# Frequency_synthesizer_v2_0.net
KiCad netlist of a schematic drawn in EAGLE
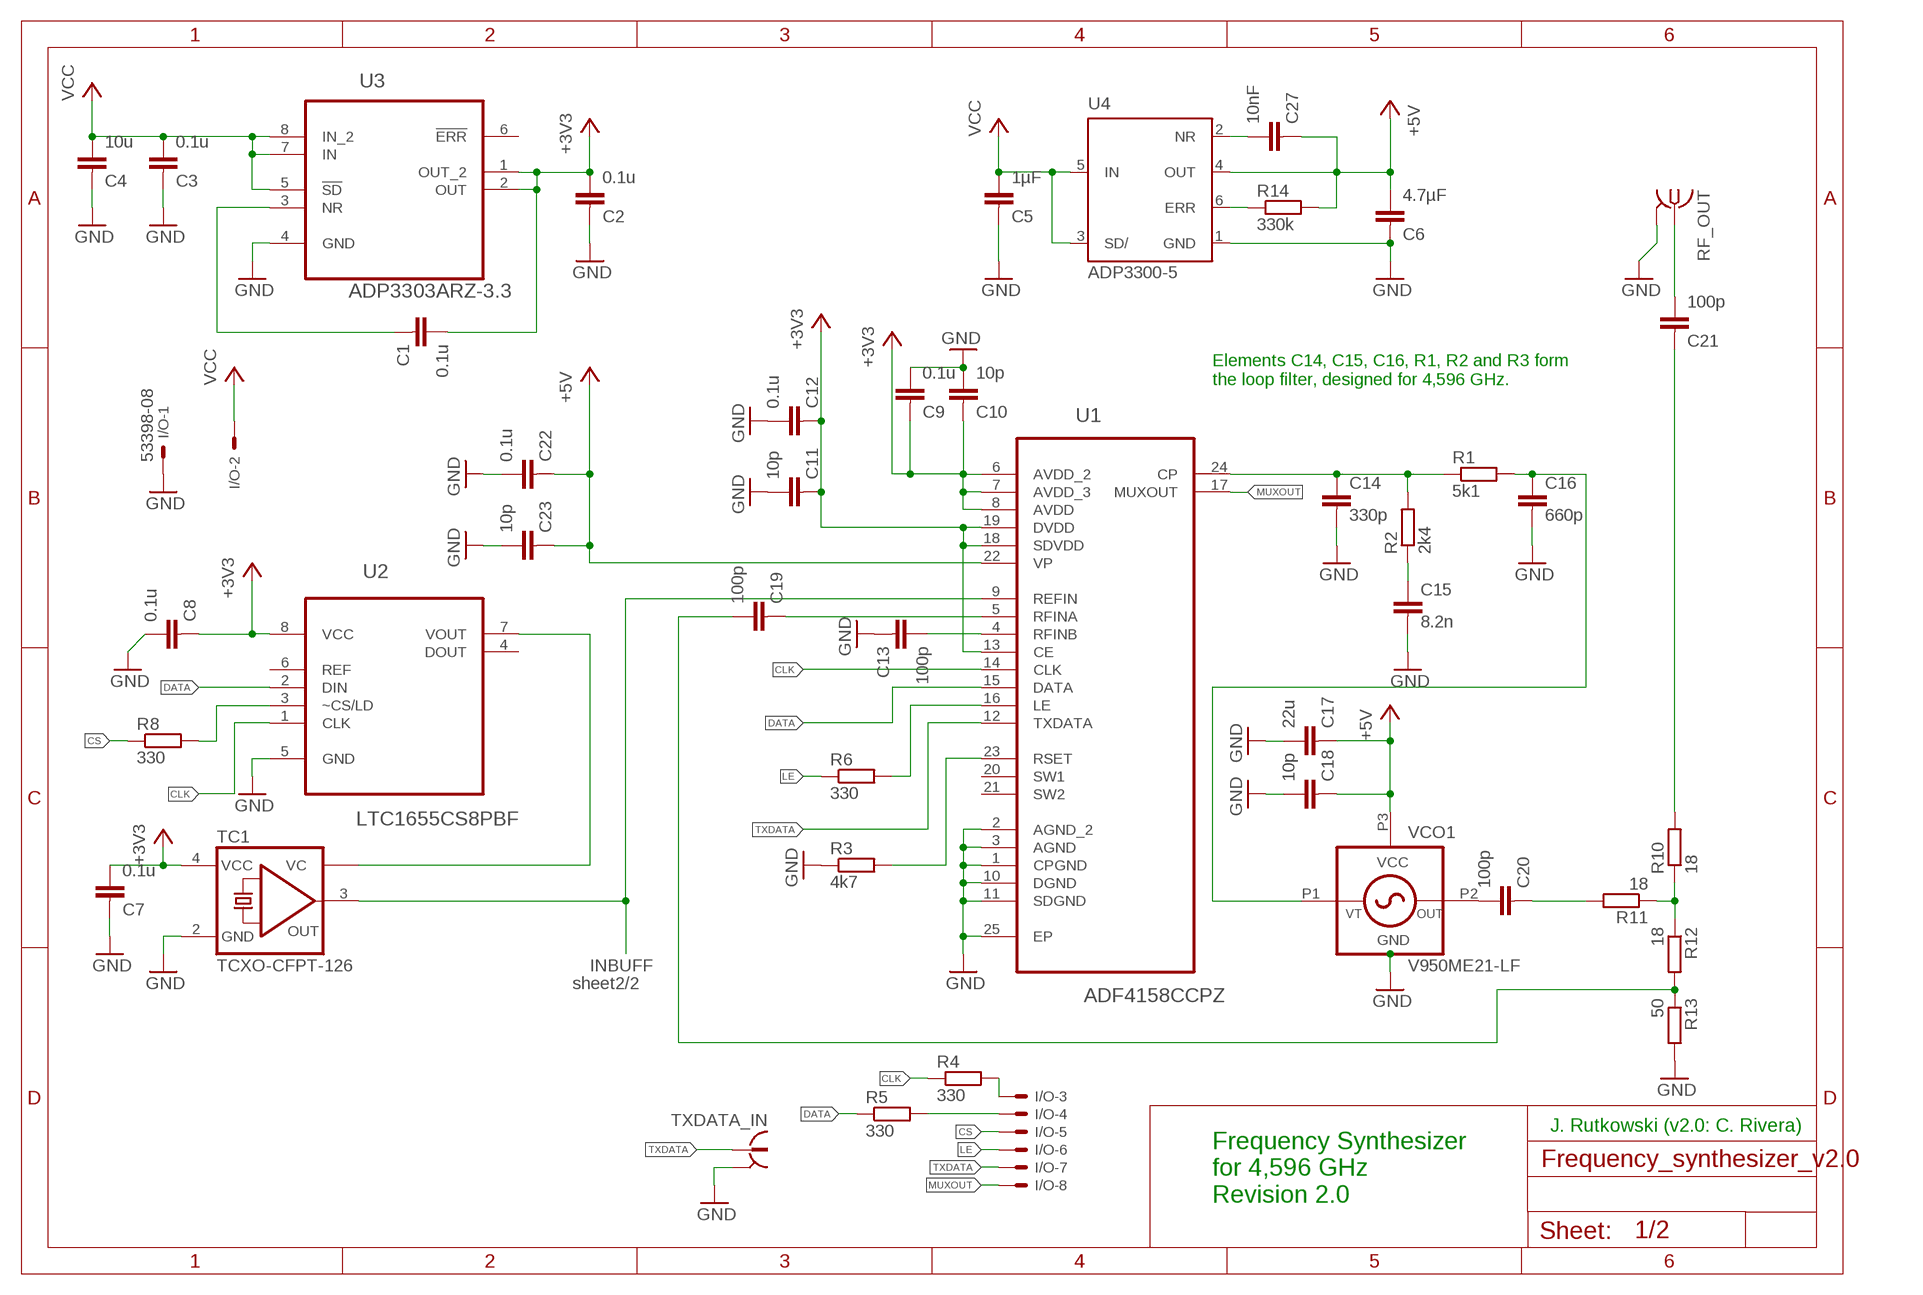
[diagram p0: schematic, sheet 1]
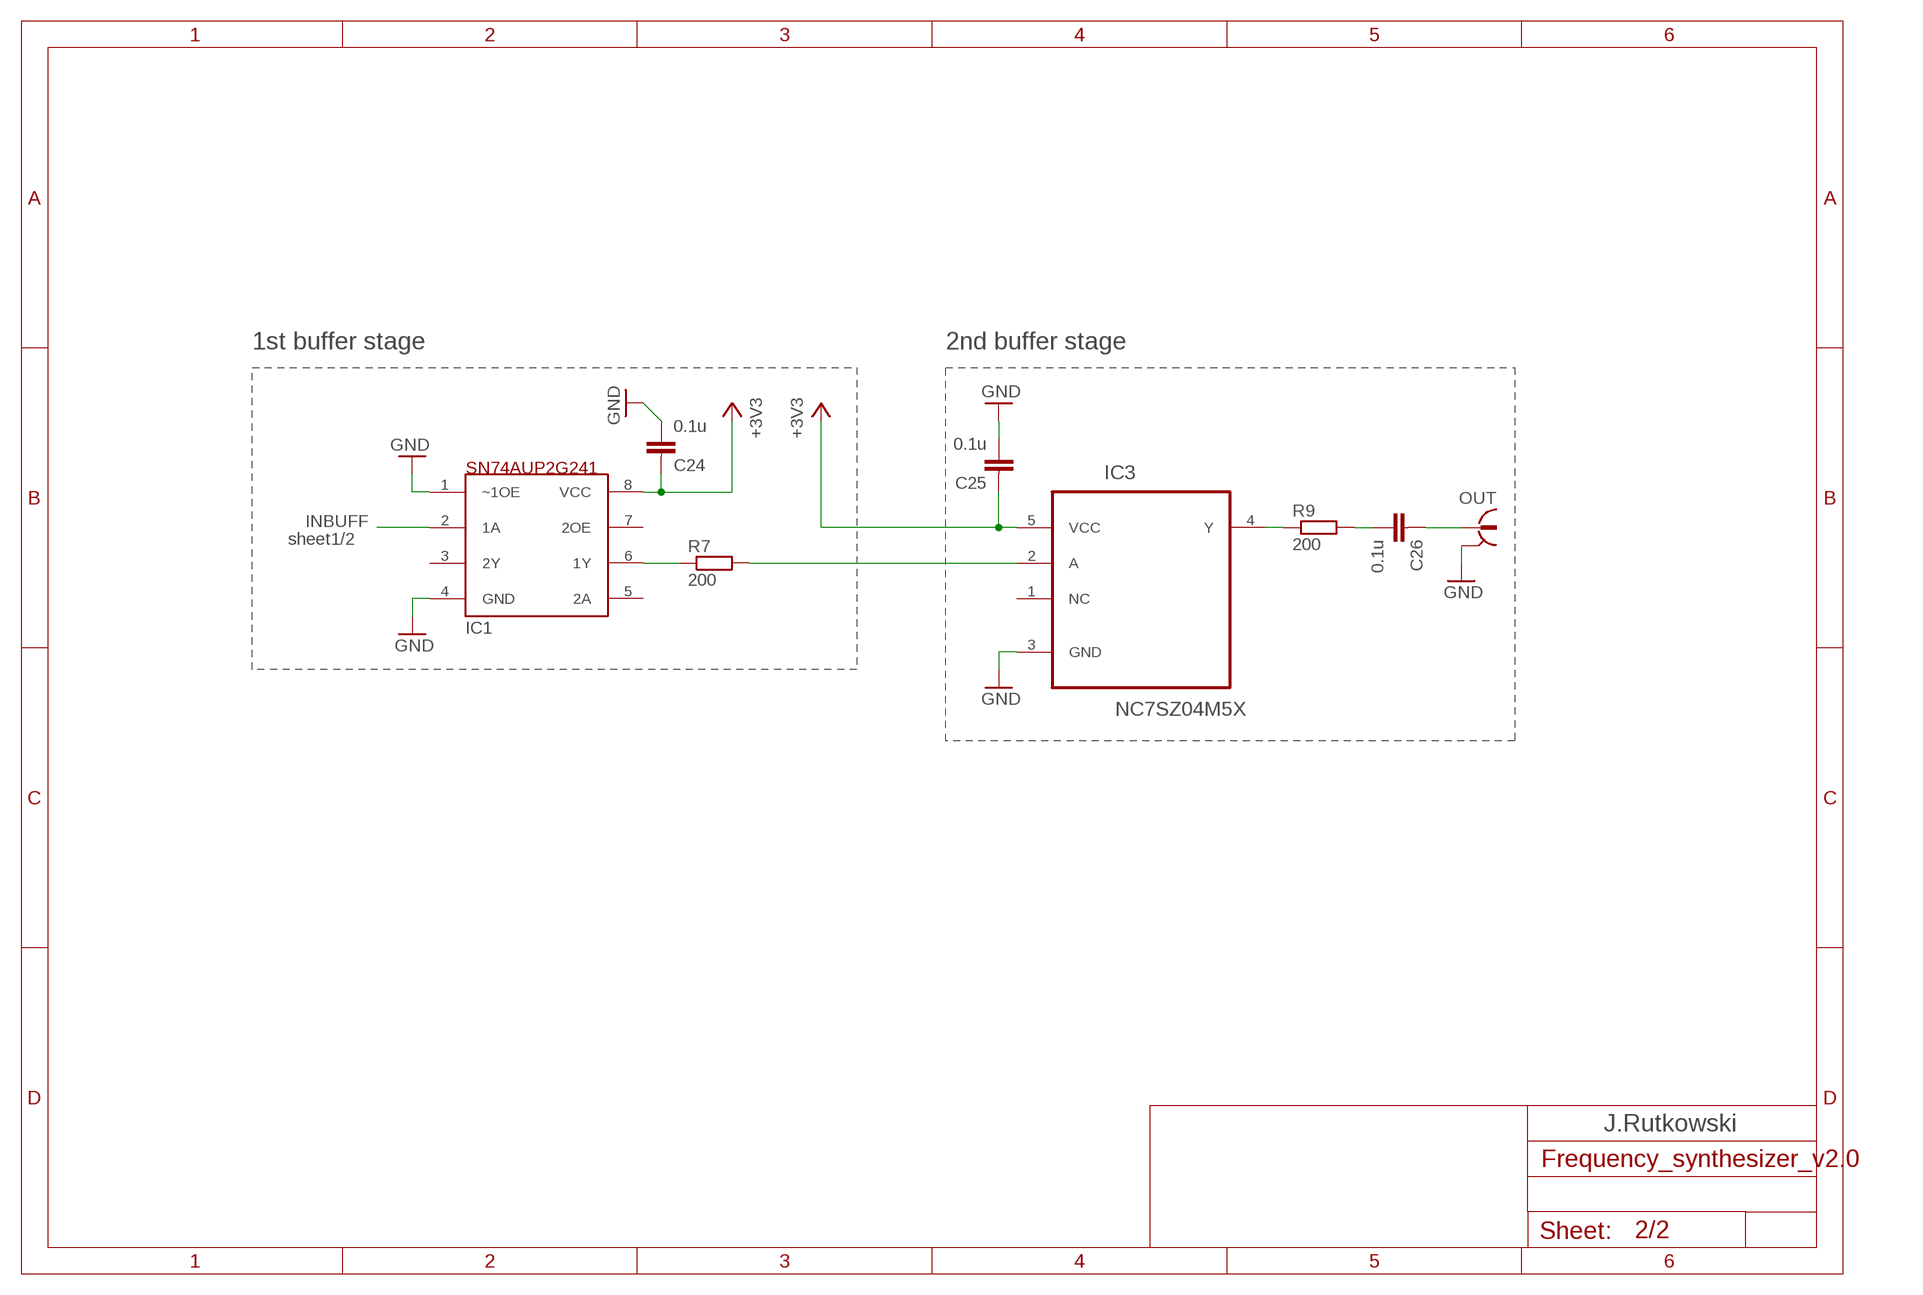
[diagram p1: schematic, sheet 2]

(export (version "E")
  (design (tool "Eeschema 10.0.6"))
  (components
    (comp (ref "C1")
      (value "0.1u")
      (footprint "eagle-import:C0603K")
      (libsource (lib "eagle-import") (part "C-EUC0603K"))
    )
    (comp (ref "C2")
      (value "0.1u")
      (footprint "eagle-import:C0603K")
      (libsource (lib "eagle-import") (part "C-EUC0603K"))
    )
    (comp (ref "C3")
      (value "0.1u")
      (footprint "eagle-import:C0603K")
      (libsource (lib "eagle-import") (part "C-EUC0603K"))
    )
    (comp (ref "C4")
      (value "10u")
      (footprint "eagle-import:C0805K")
      (libsource (lib "eagle-import") (part "C-EUC0805K"))
    )
    (comp (ref "C5")
      (value "1µF")
      (footprint "eagle-import:C0603K")
      (libsource (lib "eagle-import") (part "C-EUC0603K"))
    )
    (comp (ref "C6")
      (value "4.7µF")
      (footprint "eagle-import:C0603K")
      (libsource (lib "eagle-import") (part "C-EUC0603K"))
    )
    (comp (ref "C7")
      (value "0.1u")
      (footprint "eagle-import:C0603K")
      (libsource (lib "eagle-import") (part "C-EUC0603K"))
    )
    (comp (ref "C8")
      (value "0.1u")
      (footprint "eagle-import:C0603K")
      (libsource (lib "eagle-import") (part "C-EUC0603K"))
    )
    (comp (ref "C9")
      (value "0.1u")
      (footprint "eagle-import:C0603K")
      (libsource (lib "eagle-import") (part "C-EUC0603K"))
    )
    (comp (ref "C10")
      (value "10p")
      (footprint "eagle-import:C0603K")
      (libsource (lib "eagle-import") (part "C-EUC0603K"))
    )
    (comp (ref "C11")
      (value "10p")
      (footprint "eagle-import:C0603K")
      (libsource (lib "eagle-import") (part "C-EUC0603K"))
    )
    (comp (ref "C12")
      (value "0.1u")
      (footprint "eagle-import:C0603K")
      (libsource (lib "eagle-import") (part "C-EUC0603K"))
    )
    (comp (ref "C13")
      (value "100p")
      (footprint "eagle-import:C0402")
      (libsource (lib "eagle-import") (part "C-EUC0402"))
    )
    (comp (ref "C14")
      (value "330p")
      (footprint "eagle-import:C0603K")
      (libsource (lib "eagle-import") (part "C-EUC0603K"))
    )
    (comp (ref "C15")
      (value "8.2n")
      (footprint "eagle-import:C0603K")
      (libsource (lib "eagle-import") (part "C-EUC0603K"))
    )
    (comp (ref "C16")
      (value "660p")
      (footprint "eagle-import:C0603K")
      (libsource (lib "eagle-import") (part "C-EUC0603K"))
    )
    (comp (ref "C17")
      (value "22u")
      (footprint "eagle-import:C0805")
      (libsource (lib "eagle-import") (part "C-EUC0805"))
    )
    (comp (ref "C18")
      (value "10p")
      (footprint "eagle-import:C0603K")
      (libsource (lib "eagle-import") (part "C-EUC0603K"))
    )
    (comp (ref "C19")
      (value "100p")
      (footprint "eagle-import:C0402")
      (libsource (lib "eagle-import") (part "C-EUC0402"))
    )
    (comp (ref "C20")
      (value "100p")
      (footprint "eagle-import:C0402")
      (libsource (lib "eagle-import") (part "C-EUC0402"))
    )
    (comp (ref "C21")
      (value "100p")
      (footprint "eagle-import:C0402")
      (libsource (lib "eagle-import") (part "C-EUC0402"))
    )
    (comp (ref "C22")
      (value "0.1u")
      (footprint "eagle-import:C0603K")
      (libsource (lib "eagle-import") (part "C-EUC0603K"))
    )
    (comp (ref "C23")
      (value "10p")
      (footprint "eagle-import:C0603K")
      (libsource (lib "eagle-import") (part "C-EUC0603K"))
    )
    (comp (ref "C27")
      (value "10nF")
      (footprint "eagle-import:C0603K")
      (libsource (lib "eagle-import") (part "C-EUC0603K"))
    )
    (comp (ref "I/O")
      (value "53398-08")
      (footprint "eagle-import:53398-08")
      (libsource (lib "eagle-import") (part "53?-08398"))
    )
    (comp (ref "R1")
      (value "5k1")
      (footprint "eagle-import:R0603")
      (libsource (lib "eagle-import") (part "R-EU_R0603"))
    )
    (comp (ref "R2")
      (value "2k4")
      (footprint "eagle-import:R0603")
      (libsource (lib "eagle-import") (part "R-EU_R0603"))
    )
    (comp (ref "R3")
      (value "4k7")
      (footprint "eagle-import:R0603")
      (libsource (lib "eagle-import") (part "R-EU_R0603"))
    )
    (comp (ref "R4")
      (value "330")
      (footprint "eagle-import:R0603")
      (libsource (lib "eagle-import") (part "R-EU_R0603"))
    )
    (comp (ref "R5")
      (value "330")
      (footprint "eagle-import:R0603")
      (libsource (lib "eagle-import") (part "R-EU_R0603"))
    )
    (comp (ref "R6")
      (value "330")
      (footprint "eagle-import:R0603")
      (libsource (lib "eagle-import") (part "R-EU_R0603"))
    )
    (comp (ref "R8")
      (value "330")
      (footprint "eagle-import:R0603")
      (libsource (lib "eagle-import") (part "R-EU_R0603"))
    )
    (comp (ref "R10")
      (value "18")
      (footprint "eagle-import:R0402")
      (libsource (lib "eagle-import") (part "R-EU_R0402"))
    )
    (comp (ref "R11")
      (value "18")
      (footprint "eagle-import:R0402")
      (libsource (lib "eagle-import") (part "R-EU_R0402"))
    )
    (comp (ref "R12")
      (value "18")
      (footprint "eagle-import:R0402")
      (libsource (lib "eagle-import") (part "R-EU_R0402"))
    )
    (comp (ref "R13")
      (value "50")
      (footprint "eagle-import:R0402")
      (libsource (lib "eagle-import") (part "R-EU_R0402"))
    )
    (comp (ref "R14")
      (value "330k")
      (footprint "eagle-import:R0603")
      (libsource (lib "eagle-import") (part "R-EU_R0603"))
    )
    (comp (ref "RF_OUT")
      (value "SMA-142-0711-871/876")
      (footprint "eagle-import:J502-ND-142-0711-871_876")
      (fields (field (name "MF") "JOHNSON COMPONENTS") (field (name "MPN") "142-0711-871"))
      (libsource (lib "eagle-import") (part "SMA-142-0711-871/876"))
    )
    (comp (ref "TC1")
      (value "TCXO-CFPT-126")
      (footprint "eagle-import:7.0X5.0-4-PAD")
      (libsource (lib "eagle-import") (part "TCXO-CFPT-126"))
    )
    (comp (ref "TXDATA_IN")
      (value "734120110")
      (footprint "eagle-import:734120110")
      (libsource (lib "eagle-import") (part "734120110"))
    )
    (comp (ref "U1")
      (value "ADF4158CCPZ")
      (footprint "eagle-import:QFN50P400X400X80-25N")
      (libsource (lib "eagle-import") (part "ADF4158CCPZ"))
    )
    (comp (ref "U2")
      (value "LTC1655CS8PBF")
      (footprint "eagle-import:SOIC127P600X175-8N")
      (fields (field (name "MPN") "LTC1655CS8#PBF"))
      (libsource (lib "eagle-import") (part "LTC1655CS8PBF"))
    )
    (comp (ref "U3")
      (value "ADP3303ARZ-3.3")
      (footprint "eagle-import:SOIC127P600X175-8N")
      (libsource (lib "eagle-import") (part "ADP3303ARZ-3.3"))
    )
    (comp (ref "U4")
      (value "ADP3300-5")
      (footprint "eagle-import:SOT23-6")
      (libsource (lib "eagle-import") (part "ADP3300-5"))
    )
    (comp (ref "VCO1")
      (value "V950ME21-LF")
      (footprint "eagle-import:MINI-14S")
      (libsource (lib "eagle-import") (part "MINI-14S"))
    )
    (comp (ref "C24")
      (value "0.1u")
      (footprint "eagle-import:C0603K")
      (libsource (lib "eagle-import") (part "C-EUC0603K"))
    )
    (comp (ref "C25")
      (value "0.1u")
      (footprint "eagle-import:C0603K")
      (libsource (lib "eagle-import") (part "C-EUC0603K"))
    )
    (comp (ref "C26")
      (value "0.1u")
      (footprint "eagle-import:C0603K")
      (libsource (lib "eagle-import") (part "C-EUC0603K"))
    )
    (comp (ref "IC1")
      (value "SN74AUP2G241")
      (footprint "eagle-import:DCU_(R-PDSO-G8)")
      (libsource (lib "eagle-import") (part "SN74AUP2G241"))
    )
    (comp (ref "IC3")
      (value "NC7SZ04M5X")
      (footprint "eagle-import:SOT95P280X145-5N")
      (libsource (lib "eagle-import") (part "NC7SZ04M5X"))
    )
    (comp (ref "OUT")
      (value "734120110")
      (footprint "eagle-import:734120110")
      (libsource (lib "eagle-import") (part "734120110"))
    )
    (comp (ref "R7")
      (value "200")
      (footprint "eagle-import:R0603")
      (libsource (lib "eagle-import") (part "R-EU_R0603"))
    )
    (comp (ref "R9")
      (value "200")
      (footprint "eagle-import:R0603")
      (libsource (lib "eagle-import") (part "R-EU_R0603"))
    )
  )
  (nets
    (net (code "1") (name "+3V3") (class "Default")
      (node (ref "C1") (pin "1") (pinfunction "1_1") (pintype "passive"))
      (node (ref "C10") (pin "2") (pinfunction "2_2") (pintype "passive"))
      (node (ref "C11") (pin "2") (pinfunction "2_2") (pintype "passive"))
      (node (ref "C12") (pin "2") (pinfunction "2_2") (pintype "passive"))
      (node (ref "C2") (pin "1") (pinfunction "1_1") (pintype "passive"))
      (node (ref "C24") (pin "2") (pinfunction "2_2") (pintype "passive"))
      (node (ref "C25") (pin "2") (pinfunction "2_2") (pintype "passive"))
      (node (ref "C7") (pin "1") (pinfunction "1_1") (pintype "passive"))
      (node (ref "C8") (pin "2") (pinfunction "2_2") (pintype "passive"))
      (node (ref "C9") (pin "2") (pinfunction "2_2") (pintype "passive"))
      (node (ref "IC1") (pin "8") (pinfunction "VCC_8") (pintype "bidirectional"))
      (node (ref "IC3") (pin "5") (pinfunction "VCC_5") (pintype "power_in"))
      (node (ref "TC1") (pin "4") (pinfunction "VCC_4") (pintype "power_in"))
      (node (ref "U1") (pin "13") (pinfunction "CE_13") (pintype "input"))
      (node (ref "U1") (pin "18") (pinfunction "SDVDD_18") (pintype "power_in"))
      (node (ref "U1") (pin "19") (pinfunction "DVDD_19") (pintype "power_in"))
      (node (ref "U1") (pin "6") (pinfunction "AVDD_2_6") (pintype "power_in"))
      (node (ref "U1") (pin "7") (pinfunction "AVDD_3_7") (pintype "power_in"))
      (node (ref "U1") (pin "8") (pinfunction "AVDD_8") (pintype "power_in"))
      (node (ref "U2") (pin "8") (pinfunction "VCC_8") (pintype "power_in"))
      (node (ref "U3") (pin "1") (pinfunction "OUT_2_1") (pintype "output"))
      (node (ref "U3") (pin "2") (pinfunction "OUT_2") (pintype "output"))
    )
    (net (code "2") (name "+5V") (class "Default")
      (node (ref "C17") (pin "2") (pinfunction "2_2") (pintype "passive"))
      (node (ref "C18") (pin "2") (pinfunction "2_2") (pintype "passive"))
      (node (ref "C22") (pin "2") (pinfunction "2_2") (pintype "passive"))
      (node (ref "C23") (pin "2") (pinfunction "2_2") (pintype "passive"))
      (node (ref "C27") (pin "2") (pinfunction "2_2") (pintype "passive"))
      (node (ref "C6") (pin "1") (pinfunction "1_1") (pintype "passive"))
      (node (ref "R14") (pin "2") (pinfunction "2_2") (pintype "passive"))
      (node (ref "U1") (pin "22") (pinfunction "VP_22") (pintype "power_in"))
      (node (ref "U4") (pin "4") (pinfunction "OUT_4") (pintype "output"))
      (node (ref "VCO1") (pin "P3") (pinfunction "VCC_P3") (pintype "power_in"))
    )
    (net (code "3") (name "CLK") (class "Default")
      (node (ref "R4") (pin "1") (pinfunction "1_1") (pintype "passive"))
      (node (ref "U1") (pin "14") (pinfunction "CLK_14") (pintype "input"))
      (node (ref "U2") (pin "1") (pinfunction "CLK_1") (pintype "input"))
    )
    (net (code "4") (name "CS") (class "Default")
      (node (ref "I/O") (pin "5") (pinfunction "S_5") (pintype "passive"))
      (node (ref "R8") (pin "1") (pinfunction "1_1") (pintype "passive"))
    )
    (net (code "5") (name "DATA") (class "Default")
      (node (ref "R5") (pin "1") (pinfunction "1_1") (pintype "passive"))
      (node (ref "U1") (pin "15") (pinfunction "DATA_15") (pintype "input"))
      (node (ref "U2") (pin "2") (pinfunction "DIN_2") (pintype "input"))
    )
    (net (code "6") (name "GND") (class "Default")
      (node (ref "C10") (pin "1") (pinfunction "1_1") (pintype "passive"))
      (node (ref "C11") (pin "1") (pinfunction "1_1") (pintype "passive"))
      (node (ref "C12") (pin "1") (pinfunction "1_1") (pintype "passive"))
      (node (ref "C13") (pin "2") (pinfunction "2_2") (pintype "passive"))
      (node (ref "C14") (pin "2") (pinfunction "2_2") (pintype "passive"))
      (node (ref "C15") (pin "2") (pinfunction "2_2") (pintype "passive"))
      (node (ref "C16") (pin "2") (pinfunction "2_2") (pintype "passive"))
      (node (ref "C17") (pin "1") (pinfunction "1_1") (pintype "passive"))
      (node (ref "C18") (pin "1") (pinfunction "1_1") (pintype "passive"))
      (node (ref "C2") (pin "2") (pinfunction "2_2") (pintype "passive"))
      (node (ref "C22") (pin "1") (pinfunction "1_1") (pintype "passive"))
      (node (ref "C23") (pin "1") (pinfunction "1_1") (pintype "passive"))
      (node (ref "C24") (pin "1") (pinfunction "1_1") (pintype "passive"))
      (node (ref "C25") (pin "1") (pinfunction "1_1") (pintype "passive"))
      (node (ref "C3") (pin "2") (pinfunction "2_2") (pintype "passive"))
      (node (ref "C4") (pin "2") (pinfunction "2_2") (pintype "passive"))
      (node (ref "C5") (pin "2") (pinfunction "2_2") (pintype "passive"))
      (node (ref "C6") (pin "2") (pinfunction "2_2") (pintype "passive"))
      (node (ref "C7") (pin "2") (pinfunction "2_2") (pintype "passive"))
      (node (ref "C8") (pin "1") (pinfunction "1_1") (pintype "passive"))
      (node (ref "C9") (pin "1") (pinfunction "1_1") (pintype "passive"))
      (node (ref "I/O") (pin "1") (pinfunction "S_1") (pintype "passive"))
      (node (ref "IC1") (pin "1") (pinfunction "~{1OE}_1") (pintype "bidirectional"))
      (node (ref "IC1") (pin "4") (pinfunction "GND_4") (pintype "bidirectional"))
      (node (ref "IC3") (pin "3") (pinfunction "GND_3") (pintype "passive"))
      (node (ref "OUT") (pin "S@1") (pinfunction "2_S@1") (pintype "passive"))
      (node (ref "OUT") (pin "S@2") (pinfunction "2_S@2") (pintype "passive"))
      (node (ref "OUT") (pin "S@3") (pinfunction "2_S@3") (pintype "passive"))
      (node (ref "R13") (pin "2") (pinfunction "2_2") (pintype "passive"))
      (node (ref "R3") (pin "1") (pinfunction "1_1") (pintype "passive"))
      (node (ref "RF_OUT") (pin "G@1") (pinfunction "2_G@1") (pintype "passive"))
      (node (ref "RF_OUT") (pin "G@2") (pinfunction "2_G@2") (pintype "passive"))
      (node (ref "RF_OUT") (pin "G@3") (pinfunction "2_G@3") (pintype "passive"))
      (node (ref "RF_OUT") (pin "G@4") (pinfunction "2_G@4") (pintype "passive"))
      (node (ref "TC1") (pin "2") (pinfunction "GND_2") (pintype "power_in"))
      (node (ref "TXDATA_IN") (pin "S@1") (pinfunction "2_S@1") (pintype "passive"))
      (node (ref "TXDATA_IN") (pin "S@2") (pinfunction "2_S@2") (pintype "passive"))
      (node (ref "TXDATA_IN") (pin "S@3") (pinfunction "2_S@3") (pintype "passive"))
      (node (ref "U1") (pin "1") (pinfunction "CPGND_1") (pintype "passive"))
      (node (ref "U1") (pin "10") (pinfunction "DGND_10") (pintype "passive"))
      (node (ref "U1") (pin "11") (pinfunction "SDGND_11") (pintype "passive"))
      (node (ref "U1") (pin "2") (pinfunction "AGND_2_2") (pintype "passive"))
      (node (ref "U1") (pin "25") (pinfunction "EP_25") (pintype "passive"))
      (node (ref "U1") (pin "3") (pinfunction "AGND_3") (pintype "passive"))
      (node (ref "U2") (pin "5") (pinfunction "GND_5") (pintype "passive"))
      (node (ref "U3") (pin "4") (pinfunction "GND_4") (pintype "passive"))
      (node (ref "U4") (pin "1") (pinfunction "GND_1") (pintype "power_in"))
      (node (ref "VCO1") (pin "S1") (pinfunction "S1_S1") (pintype "power_in"))
      (node (ref "VCO1") (pin "S10") (pinfunction "S10_S10") (pintype "power_in"))
      (node (ref "VCO1") (pin "S11") (pinfunction "S11_S11") (pintype "power_in"))
      (node (ref "VCO1") (pin "S2") (pinfunction "S2_S2") (pintype "power_in"))
      (node (ref "VCO1") (pin "S3") (pinfunction "S3_S3") (pintype "power_in"))
      (node (ref "VCO1") (pin "S4") (pinfunction "S4_S4") (pintype "power_in"))
      (node (ref "VCO1") (pin "S5") (pinfunction "S5_S5") (pintype "power_in"))
      (node (ref "VCO1") (pin "S6") (pinfunction "S6_S6") (pintype "power_in"))
      (node (ref "VCO1") (pin "S7") (pinfunction "S7_S7") (pintype "power_in"))
      (node (ref "VCO1") (pin "S8") (pinfunction "S8_S8") (pintype "power_in"))
      (node (ref "VCO1") (pin "S9") (pinfunction "S9_S9") (pintype "power_in"))
    )
    (net (code "7") (name "INBUFF") (class "Default")
      (node (ref "IC1") (pin "2") (pinfunction "1A_2") (pintype "bidirectional"))
      (node (ref "TC1") (pin "3") (pinfunction "OUT_3") (pintype "output"))
      (node (ref "U1") (pin "9") (pinfunction "REFIN_9") (pintype "input"))
    )
    (net (code "8") (name "LE") (class "Default")
      (node (ref "I/O") (pin "6") (pinfunction "S_6") (pintype "passive"))
      (node (ref "R6") (pin "1") (pinfunction "1_1") (pintype "passive"))
    )
    (net (code "9") (name "MUXOUT") (class "Default")
      (node (ref "I/O") (pin "8") (pinfunction "S_8") (pintype "passive"))
      (node (ref "U1") (pin "17") (pinfunction "MUXOUT_17") (pintype "output"))
    )
    (net (code "10") (name "Net-(C15-Pad1)") (class "Default")
      (node (ref "C15") (pin "1") (pinfunction "1_1") (pintype "passive"))
      (node (ref "R2") (pin "1") (pinfunction "1_1") (pintype "passive"))
    )
    (net (code "11") (name "Net-(C19-Pad1)") (class "Default")
      (node (ref "C19") (pin "1") (pinfunction "1_1") (pintype "passive"))
      (node (ref "R12") (pin "2") (pinfunction "2_2") (pintype "passive"))
      (node (ref "R13") (pin "1") (pinfunction "1_1") (pintype "passive"))
    )
    (net (code "12") (name "Net-(C20-Pad2)") (class "Default")
      (node (ref "C20") (pin "2") (pinfunction "2_2") (pintype "passive"))
      (node (ref "R11") (pin "2") (pinfunction "2_2") (pintype "passive"))
    )
    (net (code "13") (name "Net-(C21-Pad1)") (class "Default")
      (node (ref "C21") (pin "1") (pinfunction "1_1") (pintype "passive"))
      (node (ref "RF_OUT") (pin "1") (pinfunction "1_1") (pintype "passive"))
    )
    (net (code "14") (name "Net-(C21-Pad2)") (class "Default")
      (node (ref "C21") (pin "2") (pinfunction "2_2") (pintype "passive"))
      (node (ref "R10") (pin "2") (pinfunction "2_2") (pintype "passive"))
    )
    (net (code "15") (name "Net-(C26-Pad1)") (class "Default")
      (node (ref "C26") (pin "1") (pinfunction "1_1") (pintype "passive"))
      (node (ref "R9") (pin "2") (pinfunction "2_2") (pintype "passive"))
    )
    (net (code "16") (name "Net-(C26-Pad2)") (class "Default")
      (node (ref "C26") (pin "2") (pinfunction "2_2") (pintype "passive"))
      (node (ref "OUT") (pin "1") (pinfunction "1_1") (pintype "passive"))
    )
    (net (code "17") (name "Net-(I/OC-S)") (class "Default")
      (node (ref "I/O") (pin "3") (pinfunction "S_3") (pintype "passive"))
      (node (ref "R4") (pin "2") (pinfunction "2_2") (pintype "passive"))
    )
    (net (code "18") (name "Net-(I/OD-S)") (class "Default")
      (node (ref "I/O") (pin "4") (pinfunction "S_4") (pintype "passive"))
      (node (ref "R5") (pin "2") (pinfunction "2_2") (pintype "passive"))
    )
    (net (code "19") (name "Net-(IC1-1Y)") (class "Default")
      (node (ref "IC1") (pin "6") (pinfunction "1Y_6") (pintype "bidirectional"))
      (node (ref "R7") (pin "1") (pinfunction "1_1") (pintype "passive"))
    )
    (net (code "20") (name "Net-(IC3-A)") (class "Default")
      (node (ref "IC3") (pin "2") (pinfunction "A_2") (pintype "input"))
      (node (ref "R7") (pin "2") (pinfunction "2_2") (pintype "passive"))
    )
    (net (code "21") (name "Net-(IC3-Y)") (class "Default")
      (node (ref "IC3") (pin "4") (pinfunction "Y_4") (pintype "output"))
      (node (ref "R9") (pin "1") (pinfunction "1_1") (pintype "passive"))
    )
    (net (code "22") (name "Net-(R10-Pad1)") (class "Default")
      (node (ref "R10") (pin "1") (pinfunction "1_1") (pintype "passive"))
      (node (ref "R11") (pin "1") (pinfunction "1_1") (pintype "passive"))
      (node (ref "R12") (pin "1") (pinfunction "1_1") (pintype "passive"))
    )
    (net (code "23") (name "Net-(TC1-VC)") (class "Default")
      (node (ref "TC1") (pin "1") (pinfunction "VC_1") (pintype "input"))
      (node (ref "U2") (pin "7") (pinfunction "VOUT_7") (pintype "output"))
    )
    (net (code "24") (name "Net-(U1-CP)") (class "Default")
      (node (ref "C14") (pin "1") (pinfunction "1_1") (pintype "passive"))
      (node (ref "R1") (pin "1") (pinfunction "1_1") (pintype "passive"))
      (node (ref "R2") (pin "2") (pinfunction "2_2") (pintype "passive"))
      (node (ref "U1") (pin "24") (pinfunction "CP_24") (pintype "output"))
    )
    (net (code "25") (name "Net-(U1-LE)") (class "Default")
      (node (ref "R6") (pin "2") (pinfunction "2_2") (pintype "passive"))
      (node (ref "U1") (pin "16") (pinfunction "LE_16") (pintype "input"))
    )
    (net (code "26") (name "Net-(U1-RFINA)") (class "Default")
      (node (ref "C19") (pin "2") (pinfunction "2_2") (pintype "passive"))
      (node (ref "U1") (pin "5") (pinfunction "RFINA_5") (pintype "input"))
    )
    (net (code "27") (name "Net-(U1-RFINB)") (class "Default")
      (node (ref "C13") (pin "1") (pinfunction "1_1") (pintype "passive"))
      (node (ref "U1") (pin "4") (pinfunction "RFINB_4") (pintype "input"))
    )
    (net (code "28") (name "Net-(U1-RSET)") (class "Default")
      (node (ref "R3") (pin "2") (pinfunction "2_2") (pintype "passive"))
      (node (ref "U1") (pin "23") (pinfunction "RSET_23") (pintype "passive"))
    )
    (net (code "29") (name "Net-(U2-~{CS{slash}LD})") (class "Default")
      (node (ref "R8") (pin "2") (pinfunction "2_2") (pintype "passive"))
      (node (ref "U2") (pin "3") (pinfunction "~{CS/LD}_3") (pintype "input"))
    )
    (net (code "30") (name "Net-(U3-NR)") (class "Default")
      (node (ref "C1") (pin "2") (pinfunction "2_2") (pintype "passive"))
      (node (ref "U3") (pin "3") (pinfunction "NR_3") (pintype "input"))
    )
    (net (code "31") (name "Net-(U4-ERR)") (class "Default")
      (node (ref "R14") (pin "1") (pinfunction "1_1") (pintype "passive"))
      (node (ref "U4") (pin "6") (pinfunction "ERR_6") (pintype "output"))
    )
    (net (code "32") (name "Net-(U4-NR)") (class "Default")
      (node (ref "C27") (pin "1") (pinfunction "1_1") (pintype "passive"))
      (node (ref "U4") (pin "2") (pinfunction "NR_2") (pintype "output"))
    )
    (net (code "33") (name "Net-(VCO1-OUT)") (class "Default")
      (node (ref "C20") (pin "1") (pinfunction "1_1") (pintype "passive"))
      (node (ref "VCO1") (pin "P2") (pinfunction "OUT_P2") (pintype "output"))
    )
    (net (code "34") (name "Net-(VCO1-VT)") (class "Default")
      (node (ref "C16") (pin "1") (pinfunction "1_1") (pintype "passive"))
      (node (ref "R1") (pin "2") (pinfunction "2_2") (pintype "passive"))
      (node (ref "VCO1") (pin "P1") (pinfunction "VT_P1") (pintype "input"))
    )
    (net (code "35") (name "TXDATA") (class "Default")
      (node (ref "I/O") (pin "7") (pinfunction "S_7") (pintype "passive"))
      (node (ref "TXDATA_IN") (pin "1") (pinfunction "1_1") (pintype "passive"))
      (node (ref "U1") (pin "12") (pinfunction "TXDATA_12") (pintype "input"))
    )
    (net (code "36") (name "VCC") (class "Default")
      (node (ref "C3") (pin "1") (pinfunction "1_1") (pintype "passive"))
      (node (ref "C4") (pin "1") (pinfunction "1_1") (pintype "passive"))
      (node (ref "C5") (pin "1") (pinfunction "1_1") (pintype "passive"))
      (node (ref "I/O") (pin "2") (pinfunction "S_2") (pintype "passive"))
      (node (ref "U3") (pin "5") (pinfunction "~{SD}_5") (pintype "input"))
      (node (ref "U3") (pin "7") (pinfunction "IN_7") (pintype "input"))
      (node (ref "U3") (pin "8") (pinfunction "IN_2_8") (pintype "input"))
      (node (ref "U4") (pin "3") (pinfunction "SD/_3") (pintype "bidirectional"))
      (node (ref "U4") (pin "5") (pinfunction "IN_5") (pintype "input"))
    )
    (net (code "37") (name "unconnected-(IC1-2A-Pad5)") (class "Default")
      (node (ref "IC1") (pin "5") (pinfunction "2A_5") (pintype "bidirectional"))
    )
    (net (code "38") (name "unconnected-(IC1-2OE-Pad7)") (class "Default")
      (node (ref "IC1") (pin "7") (pinfunction "2OE_7") (pintype "bidirectional"))
    )
    (net (code "39") (name "unconnected-(IC1-2Y-Pad3)") (class "Default")
      (node (ref "IC1") (pin "3") (pinfunction "2Y_3") (pintype "bidirectional"))
    )
    (net (code "40") (name "unconnected-(IC3-NC-Pad1)") (class "Default")
      (node (ref "IC3") (pin "1") (pinfunction "NC_1") (pintype "no_connect"))
    )
    (net (code "41") (name "unconnected-(U1-SW1-Pad20)") (class "Default")
      (node (ref "U1") (pin "20") (pinfunction "SW1_20") (pintype "passive"))
    )
    (net (code "42") (name "unconnected-(U1-SW2-Pad21)") (class "Default")
      (node (ref "U1") (pin "21") (pinfunction "SW2_21") (pintype "passive"))
    )
    (net (code "43") (name "unconnected-(U2-DOUT-Pad4)") (class "Default")
      (node (ref "U2") (pin "4") (pinfunction "DOUT_4") (pintype "output"))
    )
    (net (code "44") (name "unconnected-(U2-REF-Pad6)") (class "Default")
      (node (ref "U2") (pin "6") (pinfunction "REF_6") (pintype "input"))
    )
    (net (code "45") (name "unconnected-(U3-~{ERR}-Pad6)") (class "Default")
      (node (ref "U3") (pin "6") (pinfunction "~{ERR}_6") (pintype "output"))
    )
  )
)
